# CAN_Bus_Breakout_V1_0.net
KiCad netlist of a schematic drawn in EAGLE
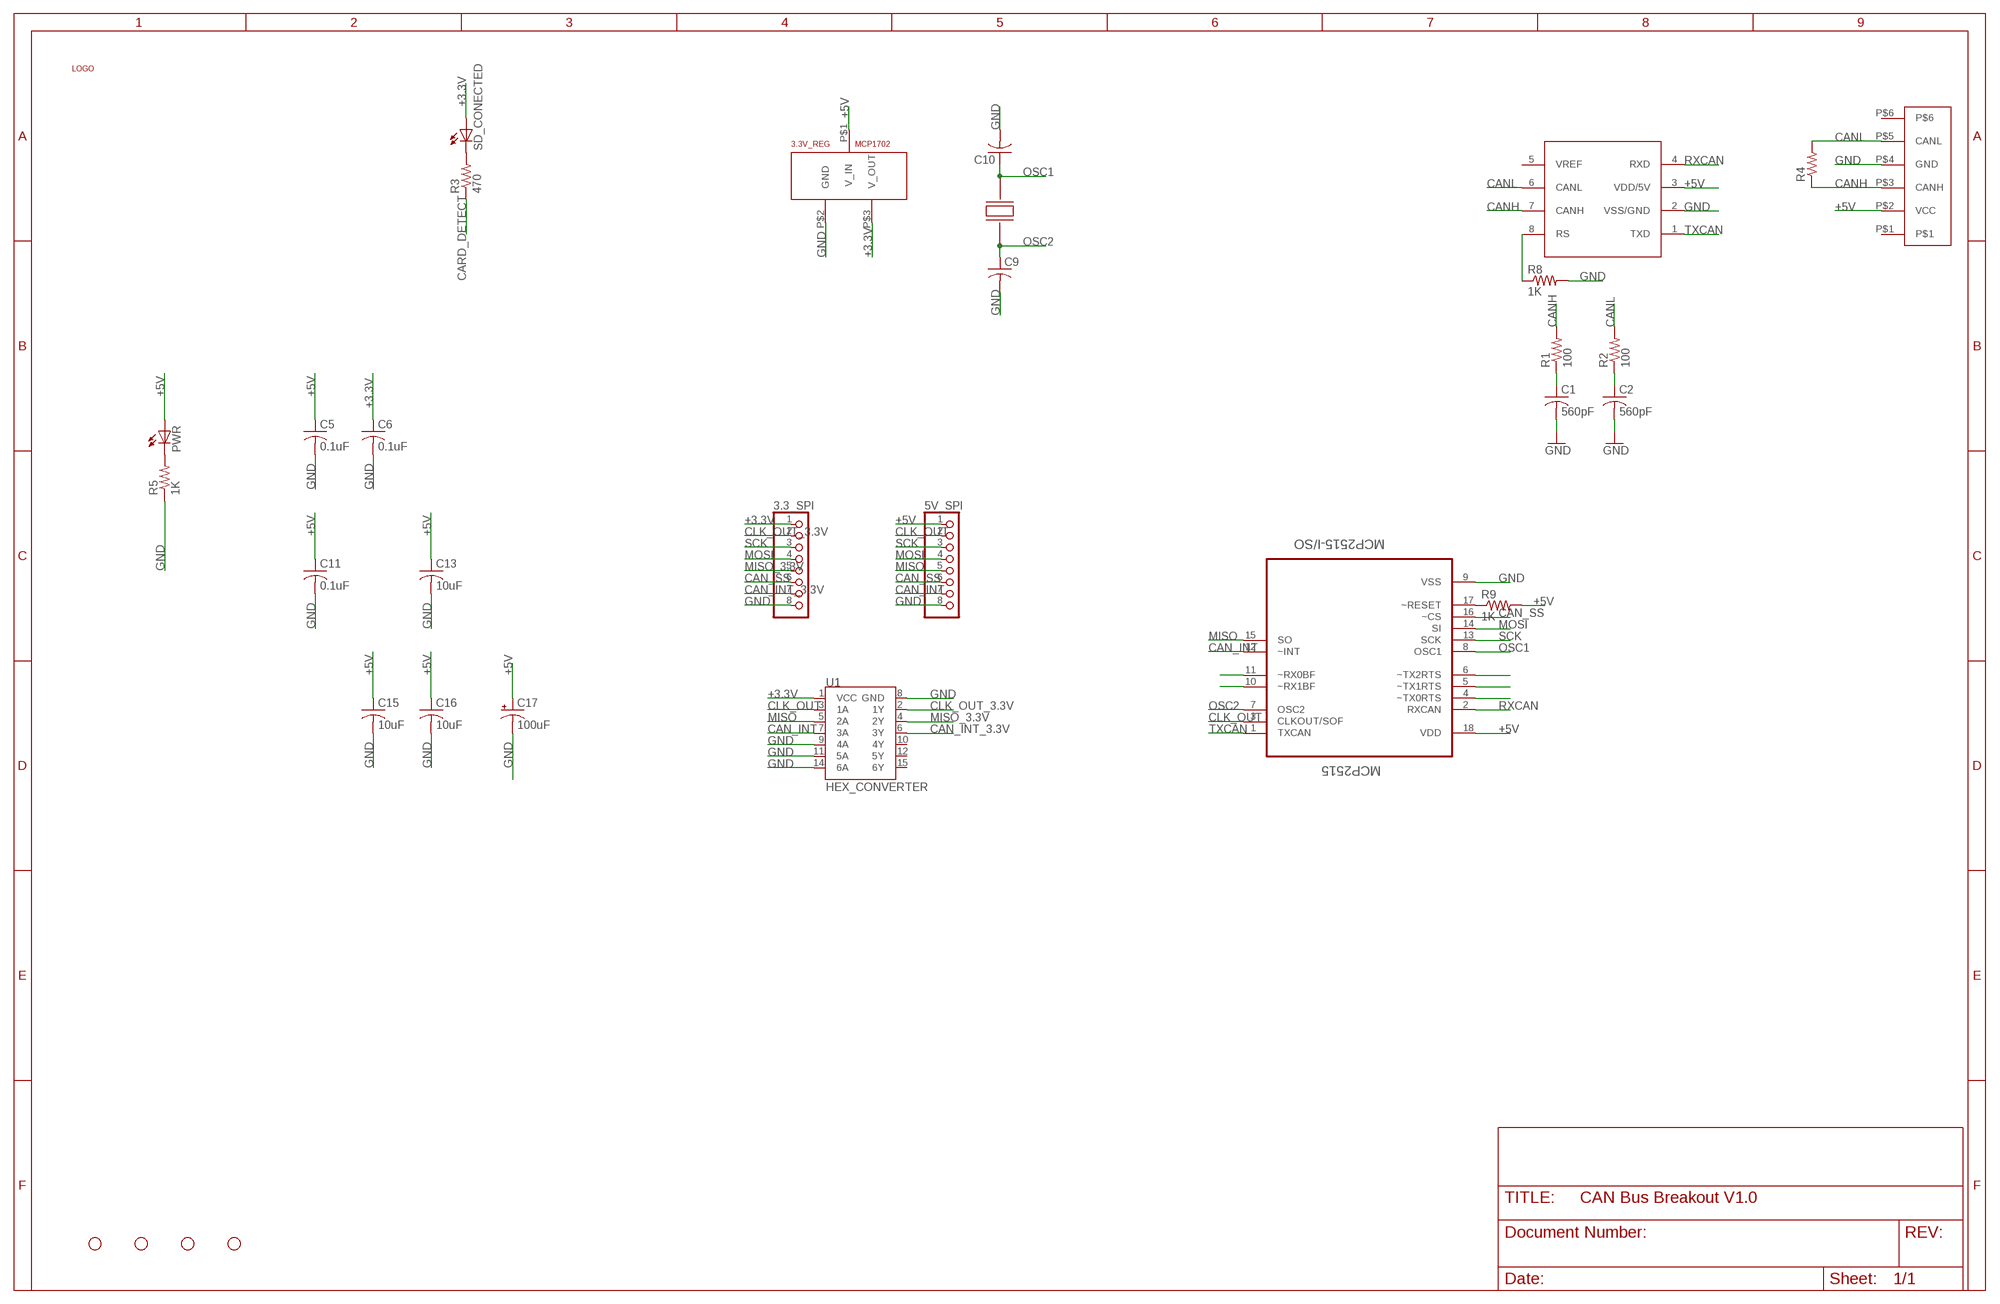
[diagram p0: schematic, sheet 1]

(export (version "E")
  (design (tool "Eeschema 10.0.6"))
  (components
    (comp (ref "3.3V_REG")
      (value "MCP1702")
      (footprint "eagle-import:SOT-23A")
      (libsource (lib "eagle-import") (part "MCP1702"))
    )
    (comp (ref "3.3_SPI")
      (value "PINHD-1X8CLEANBIG")
      (footprint "eagle-import:1X08-CLEANBIG")
      (libsource (lib "eagle-import") (part "PINHD-1X8CLEANBIG"))
    )
    (comp (ref "5V_SPI")
      (value "PINHD-1X8CLEANBIG")
      (footprint "eagle-import:1X08-CLEANBIG")
      (libsource (lib "eagle-import") (part "PINHD-1X8CLEANBIG"))
    )
    (comp (ref "C1")
      (value "560pF")
      (footprint "eagle-import:C0805")
      (libsource (lib "eagle-import") (part "C-USC0805"))
    )
    (comp (ref "C2")
      (value "560pF")
      (footprint "eagle-import:C0805")
      (libsource (lib "eagle-import") (part "C-USC0805"))
    )
    (comp (ref "C5")
      (value "0.1uF")
      (footprint "eagle-import:C0805")
      (libsource (lib "eagle-import") (part "C-USC0805"))
    )
    (comp (ref "C6")
      (value "0.1uF")
      (footprint "eagle-import:C0805")
      (libsource (lib "eagle-import") (part "C-USC0805"))
    )
    (comp (ref "C9")
      (value "C-USC0805")
      (footprint "eagle-import:C0805")
      (libsource (lib "eagle-import") (part "C-USC0805"))
    )
    (comp (ref "C10")
      (value "C-USC0805")
      (footprint "eagle-import:C0805")
      (libsource (lib "eagle-import") (part "C-USC0805"))
    )
    (comp (ref "C11")
      (value "0.1uF")
      (footprint "eagle-import:C0805")
      (libsource (lib "eagle-import") (part "C-USC0805"))
    )
    (comp (ref "C13")
      (value "10uF")
      (footprint "eagle-import:C0805")
      (libsource (lib "eagle-import") (part "C-USC0805"))
    )
    (comp (ref "C15")
      (value "10uF")
      (footprint "eagle-import:C0805")
      (libsource (lib "eagle-import") (part "C-USC0805"))
    )
    (comp (ref "C16")
      (value "10uF")
      (footprint "eagle-import:C0805")
      (libsource (lib "eagle-import") (part "C-USC0805"))
    )
    (comp (ref "C17")
      (value "100uF")
      (footprint "eagle-import:PANASONIC_D")
      (libsource (lib "eagle-import") (part "47UF-50V-20%(ELECT)"))
    )
    (comp (ref "MCP2515")
      (value "MCP2515-I/SO")
      (footprint "eagle-import:SOIC127P1034X264-18N")
      (libsource (lib "eagle-import") (part "MCP2515-I/SO"))
    )
    (comp (ref "PWR")
      (value "LED1206")
      (footprint "eagle-import:LED-1206")
      (libsource (lib "eagle-import") (part "LED1206"))
    )
    (comp (ref "R1")
      (value "100")
      (footprint "eagle-import:M0805")
      (libsource (lib "eagle-import") (part "R-US_M0805"))
    )
    (comp (ref "R2")
      (value "100")
      (footprint "eagle-import:M0805")
      (libsource (lib "eagle-import") (part "R-US_M0805"))
    )
    (comp (ref "R3")
      (value "470")
      (footprint "eagle-import:M0805")
      (libsource (lib "eagle-import") (part "R-US_M0805"))
    )
    (comp (ref "R4")
      (value "R-US_M0805")
      (footprint "eagle-import:M0805")
      (libsource (lib "eagle-import") (part "R-US_M0805"))
    )
    (comp (ref "R5")
      (value "1K")
      (footprint "eagle-import:M0805")
      (libsource (lib "eagle-import") (part "R-US_M0805"))
    )
    (comp (ref "R8")
      (value "1K")
      (footprint "eagle-import:M0805")
      (libsource (lib "eagle-import") (part "R-US_M0805"))
    )
    (comp (ref "R9")
      (value "1K")
      (footprint "eagle-import:M0805")
      (libsource (lib "eagle-import") (part "R-US_M0805"))
    )
    (comp (ref "SD_CONECTED")
      (value "LED1206")
      (footprint "eagle-import:LED-1206")
      (libsource (lib "eagle-import") (part "LED1206"))
    )
    (comp (ref "STANDOFF1")
      (value "STAND-OFF")
      (footprint "eagle-import:STAND-OFF")
      (libsource (lib "eagle-import") (part "STAND-OFF"))
    )
    (comp (ref "STANDOFF2")
      (value "STAND-OFF")
      (footprint "eagle-import:STAND-OFF")
      (libsource (lib "eagle-import") (part "STAND-OFF"))
    )
    (comp (ref "STANDOFF3")
      (value "STAND-OFF")
      (footprint "eagle-import:STAND-OFF")
      (libsource (lib "eagle-import") (part "STAND-OFF"))
    )
    (comp (ref "STANDOFF4")
      (value "STAND-OFF")
      (footprint "eagle-import:STAND-OFF")
      (libsource (lib "eagle-import") (part "STAND-OFF"))
    )
    (comp (ref "U$1")
      (value "CAN_6P6C")
      (footprint "eagle-import:CAN_6P6C")
      (libsource (lib "eagle-import") (part "CAN_6P6C"))
    )
    (comp (ref "U$2")
      (value "MCP2551DIP")
      (footprint "eagle-import:DIP8")
      (libsource (lib "eagle-import") (part "MCP2551DIP"))
    )
    (comp (ref "U$3")
      (value "LOGO")
      (footprint "eagle-import:LOGO")
      (libsource (lib "eagle-import") (part "LOGO"))
    )
    (comp (ref "U$19")
      (value "CRYSTAL")
      (footprint "eagle-import:7A_CRYSTAL")
      (libsource (lib "eagle-import") (part "CRYSTAL"))
    )
    (comp (ref "U1")
      (value "HEX_CONVERTER")
      (footprint "eagle-import:SO016")
      (libsource (lib "eagle-import") (part "HEX_CONVERTER"))
    )
  )
  (nets
    (net (code "1") (name "/+3.3V") (class "Default")
      (node (ref "3.3V_REG") (pin "P$3") (pinfunction "V_OUT_P$3") (pintype "bidirectional"))
      (node (ref "3.3_SPI") (pin "1") (pinfunction "1_1") (pintype "passive"))
      (node (ref "C6") (pin "1") (pinfunction "1_1") (pintype "passive"))
      (node (ref "SD_CONECTED") (pin "A") (pinfunction "A_A") (pintype "passive"))
      (node (ref "U1") (pin "1") (pinfunction "VCC_1") (pintype "bidirectional"))
    )
    (net (code "2") (name "/+5V") (class "Default")
      (node (ref "3.3V_REG") (pin "P$1") (pinfunction "V_IN_P$1") (pintype "bidirectional"))
      (node (ref "5V_SPI") (pin "1") (pinfunction "1_1") (pintype "passive"))
      (node (ref "C11") (pin "1") (pinfunction "1_1") (pintype "passive"))
      (node (ref "C13") (pin "1") (pinfunction "1_1") (pintype "passive"))
      (node (ref "C15") (pin "1") (pinfunction "1_1") (pintype "passive"))
      (node (ref "C16") (pin "1") (pinfunction "1_1") (pintype "passive"))
      (node (ref "C17") (pin "+") (pinfunction "+_+") (pintype "passive"))
      (node (ref "C5") (pin "1") (pinfunction "1_1") (pintype "passive"))
      (node (ref "MCP2515") (pin "18") (pinfunction "VDD_18") (pintype "power_in"))
      (node (ref "PWR") (pin "A") (pinfunction "A_A") (pintype "passive"))
      (node (ref "R9") (pin "2") (pinfunction "2_2") (pintype "passive"))
      (node (ref "U$1") (pin "P$2") (pinfunction "VCC_P$2") (pintype "bidirectional"))
      (node (ref "U$2") (pin "3") (pinfunction "VDD/5V_3") (pintype "bidirectional"))
    )
    (net (code "3") (name "/CANH") (class "Default")
      (node (ref "R1") (pin "2") (pinfunction "2_2") (pintype "passive"))
      (node (ref "R4") (pin "1") (pinfunction "1_1") (pintype "passive"))
      (node (ref "U$1") (pin "P$3") (pinfunction "CANH_P$3") (pintype "bidirectional"))
      (node (ref "U$2") (pin "7") (pinfunction "CANH_7") (pintype "bidirectional"))
    )
    (net (code "4") (name "/CANL") (class "Default")
      (node (ref "R2") (pin "2") (pinfunction "2_2") (pintype "passive"))
      (node (ref "R4") (pin "2") (pinfunction "2_2") (pintype "passive"))
      (node (ref "U$1") (pin "P$5") (pinfunction "CANL_P$5") (pintype "bidirectional"))
      (node (ref "U$2") (pin "6") (pinfunction "CANL_6") (pintype "bidirectional"))
    )
    (net (code "5") (name "/CAN_INT") (class "Default")
      (node (ref "5V_SPI") (pin "7") (pinfunction "7_7") (pintype "passive"))
      (node (ref "MCP2515") (pin "12") (pinfunction "~{INT}_12") (pintype "output"))
      (node (ref "U1") (pin "7") (pinfunction "3A_7") (pintype "bidirectional"))
    )
    (net (code "6") (name "/CAN_INT_3.3V") (class "Default")
      (node (ref "3.3_SPI") (pin "7") (pinfunction "7_7") (pintype "passive"))
      (node (ref "U1") (pin "6") (pinfunction "3Y_6") (pintype "bidirectional"))
    )
    (net (code "7") (name "/CAN_SS") (class "Default")
      (node (ref "3.3_SPI") (pin "6") (pinfunction "6_6") (pintype "passive"))
      (node (ref "5V_SPI") (pin "6") (pinfunction "6_6") (pintype "passive"))
      (node (ref "MCP2515") (pin "16") (pinfunction "~{CS}_16") (pintype "input"))
    )
    (net (code "8") (name "/CARD_DETECT") (class "Default")
      (node (ref "R3") (pin "1") (pinfunction "1_1") (pintype "passive"))
    )
    (net (code "9") (name "/CLK_OUT") (class "Default")
      (node (ref "5V_SPI") (pin "2") (pinfunction "2_2") (pintype "passive"))
      (node (ref "MCP2515") (pin "3") (pinfunction "CLKOUT/SOF_3") (pintype "output"))
      (node (ref "U1") (pin "3") (pinfunction "1A_3") (pintype "bidirectional"))
    )
    (net (code "10") (name "/CLK_OUT_3.3V") (class "Default")
      (node (ref "3.3_SPI") (pin "2") (pinfunction "2_2") (pintype "passive"))
      (node (ref "U1") (pin "2") (pinfunction "1Y_2") (pintype "bidirectional"))
    )
    (net (code "11") (name "/MISO") (class "Default")
      (node (ref "5V_SPI") (pin "5") (pinfunction "5_5") (pintype "passive"))
      (node (ref "MCP2515") (pin "15") (pinfunction "SO_15") (pintype "output"))
      (node (ref "U1") (pin "5") (pinfunction "2A_5") (pintype "bidirectional"))
    )
    (net (code "12") (name "/MISO_3.3V") (class "Default")
      (node (ref "3.3_SPI") (pin "5") (pinfunction "5_5") (pintype "passive"))
      (node (ref "U1") (pin "4") (pinfunction "2Y_4") (pintype "bidirectional"))
    )
    (net (code "13") (name "/MOSI") (class "Default")
      (node (ref "3.3_SPI") (pin "4") (pinfunction "4_4") (pintype "passive"))
      (node (ref "5V_SPI") (pin "4") (pinfunction "4_4") (pintype "passive"))
      (node (ref "MCP2515") (pin "14") (pinfunction "SI_14") (pintype "input"))
    )
    (net (code "14") (name "/OSC1") (class "Default")
      (node (ref "C10") (pin "1") (pinfunction "1_1") (pintype "passive"))
      (node (ref "MCP2515") (pin "8") (pinfunction "OSC1_8") (pintype "input"))
      (node (ref "U$19") (pin "P$2") (pinfunction "P$2_P$2") (pintype "bidirectional"))
    )
    (net (code "15") (name "/OSC2") (class "Default")
      (node (ref "C9") (pin "1") (pinfunction "1_1") (pintype "passive"))
      (node (ref "MCP2515") (pin "7") (pinfunction "OSC2_7") (pintype "output"))
      (node (ref "U$19") (pin "P$1") (pinfunction "P$1_P$1") (pintype "bidirectional"))
    )
    (net (code "16") (name "/RXCAN") (class "Default")
      (node (ref "MCP2515") (pin "2") (pinfunction "RXCAN_2") (pintype "input"))
      (node (ref "U$2") (pin "4") (pinfunction "RXD_4") (pintype "bidirectional"))
    )
    (net (code "17") (name "/SCK") (class "Default")
      (node (ref "3.3_SPI") (pin "3") (pinfunction "3_3") (pintype "passive"))
      (node (ref "5V_SPI") (pin "3") (pinfunction "3_3") (pintype "passive"))
      (node (ref "MCP2515") (pin "13") (pinfunction "SCK_13") (pintype "input"))
    )
    (net (code "18") (name "/TXCAN") (class "Default")
      (node (ref "MCP2515") (pin "1") (pinfunction "TXCAN_1") (pintype "output"))
      (node (ref "U$2") (pin "1") (pinfunction "TXD_1") (pintype "bidirectional"))
    )
    (net (code "19") (name "GND") (class "Default")
      (node (ref "3.3V_REG") (pin "P$2") (pinfunction "GND_P$2") (pintype "bidirectional"))
      (node (ref "3.3_SPI") (pin "8") (pinfunction "8_8") (pintype "passive"))
      (node (ref "5V_SPI") (pin "8") (pinfunction "8_8") (pintype "passive"))
      (node (ref "C1") (pin "2") (pinfunction "2_2") (pintype "passive"))
      (node (ref "C10") (pin "2") (pinfunction "2_2") (pintype "passive"))
      (node (ref "C11") (pin "2") (pinfunction "2_2") (pintype "passive"))
      (node (ref "C13") (pin "2") (pinfunction "2_2") (pintype "passive"))
      (node (ref "C15") (pin "2") (pinfunction "2_2") (pintype "passive"))
      (node (ref "C16") (pin "2") (pinfunction "2_2") (pintype "passive"))
      (node (ref "C17") (pin "-") (pinfunction "-_-") (pintype "passive"))
      (node (ref "C2") (pin "2") (pinfunction "2_2") (pintype "passive"))
      (node (ref "C5") (pin "2") (pinfunction "2_2") (pintype "passive"))
      (node (ref "C6") (pin "2") (pinfunction "2_2") (pintype "passive"))
      (node (ref "C9") (pin "2") (pinfunction "2_2") (pintype "passive"))
      (node (ref "MCP2515") (pin "9") (pinfunction "VSS_9") (pintype "power_in"))
      (node (ref "R5") (pin "1") (pinfunction "1_1") (pintype "passive"))
      (node (ref "R8") (pin "2") (pinfunction "2_2") (pintype "passive"))
      (node (ref "U$1") (pin "P$4") (pinfunction "GND_P$4") (pintype "bidirectional"))
      (node (ref "U$2") (pin "2") (pinfunction "VSS/GND_2") (pintype "bidirectional"))
      (node (ref "U1") (pin "11") (pinfunction "5A_11") (pintype "bidirectional"))
      (node (ref "U1") (pin "14") (pinfunction "6A_14") (pintype "bidirectional"))
      (node (ref "U1") (pin "8") (pinfunction "GND_8") (pintype "bidirectional"))
      (node (ref "U1") (pin "9") (pinfunction "4A_9") (pintype "bidirectional"))
    )
    (net (code "20") (name "Net-(C1-Pad1)") (class "Default")
      (node (ref "C1") (pin "1") (pinfunction "1_1") (pintype "passive"))
      (node (ref "R1") (pin "1") (pinfunction "1_1") (pintype "passive"))
    )
    (net (code "21") (name "Net-(C2-Pad1)") (class "Default")
      (node (ref "C2") (pin "1") (pinfunction "1_1") (pintype "passive"))
      (node (ref "R2") (pin "1") (pinfunction "1_1") (pintype "passive"))
    )
    (net (code "22") (name "Net-(MCP2515-~{RESET})") (class "Default")
      (node (ref "MCP2515") (pin "17") (pinfunction "~{RESET}_17") (pintype "input"))
      (node (ref "R9") (pin "1") (pinfunction "1_1") (pintype "passive"))
    )
    (net (code "23") (name "Net-(PWR-PadC)") (class "Default")
      (node (ref "PWR") (pin "C") (pinfunction "C_C") (pintype "passive"))
      (node (ref "R5") (pin "2") (pinfunction "2_2") (pintype "passive"))
    )
    (net (code "24") (name "Net-(R3-Pad2)") (class "Default")
      (node (ref "R3") (pin "2") (pinfunction "2_2") (pintype "passive"))
      (node (ref "SD_CONECTED") (pin "C") (pinfunction "C_C") (pintype "passive"))
    )
    (net (code "25") (name "Net-(U$2-RS)") (class "Default")
      (node (ref "R8") (pin "1") (pinfunction "1_1") (pintype "passive"))
      (node (ref "U$2") (pin "8") (pinfunction "RS_8") (pintype "bidirectional"))
    )
    (net (code "26") (name "unconnected-(MCP2515-~{RX0BF}-Pad11)") (class "Default")
      (node (ref "MCP2515") (pin "11") (pinfunction "~{RX0BF}_11") (pintype "output"))
    )
    (net (code "27") (name "unconnected-(MCP2515-~{RX1BF}-Pad10)") (class "Default")
      (node (ref "MCP2515") (pin "10") (pinfunction "~{RX1BF}_10") (pintype "output"))
    )
    (net (code "28") (name "unconnected-(MCP2515-~{TX0RTS}-Pad4)") (class "Default")
      (node (ref "MCP2515") (pin "4") (pinfunction "~{TX0RTS}_4") (pintype "input"))
    )
    (net (code "29") (name "unconnected-(MCP2515-~{TX1RTS}-Pad5)") (class "Default")
      (node (ref "MCP2515") (pin "5") (pinfunction "~{TX1RTS}_5") (pintype "input"))
    )
    (net (code "30") (name "unconnected-(MCP2515-~{TX2RTS}-Pad6)") (class "Default")
      (node (ref "MCP2515") (pin "6") (pinfunction "~{TX2RTS}_6") (pintype "input"))
    )
    (net (code "31") (name "unconnected-(U$1-PadP$1)") (class "Default")
      (node (ref "U$1") (pin "P$1") (pinfunction "P$1_P$1") (pintype "bidirectional"))
    )
    (net (code "32") (name "unconnected-(U$1-PadP$6)") (class "Default")
      (node (ref "U$1") (pin "P$6") (pinfunction "P$6_P$6") (pintype "bidirectional"))
    )
    (net (code "33") (name "unconnected-(U$2-VREF-Pad5)") (class "Default")
      (node (ref "U$2") (pin "5") (pinfunction "VREF_5") (pintype "bidirectional"))
    )
    (net (code "34") (name "unconnected-(U1-4Y-Pad10)") (class "Default")
      (node (ref "U1") (pin "10") (pinfunction "4Y_10") (pintype "bidirectional"))
    )
    (net (code "35") (name "unconnected-(U1-5Y-Pad12)") (class "Default")
      (node (ref "U1") (pin "12") (pinfunction "5Y_12") (pintype "bidirectional"))
    )
    (net (code "36") (name "unconnected-(U1-6Y-Pad15)") (class "Default")
      (node (ref "U1") (pin "15") (pinfunction "6Y_15") (pintype "bidirectional"))
    )
  )
)
